# whare_hauora_sensor_r1.net
KiCad netlist of a schematic drawn in EAGLE
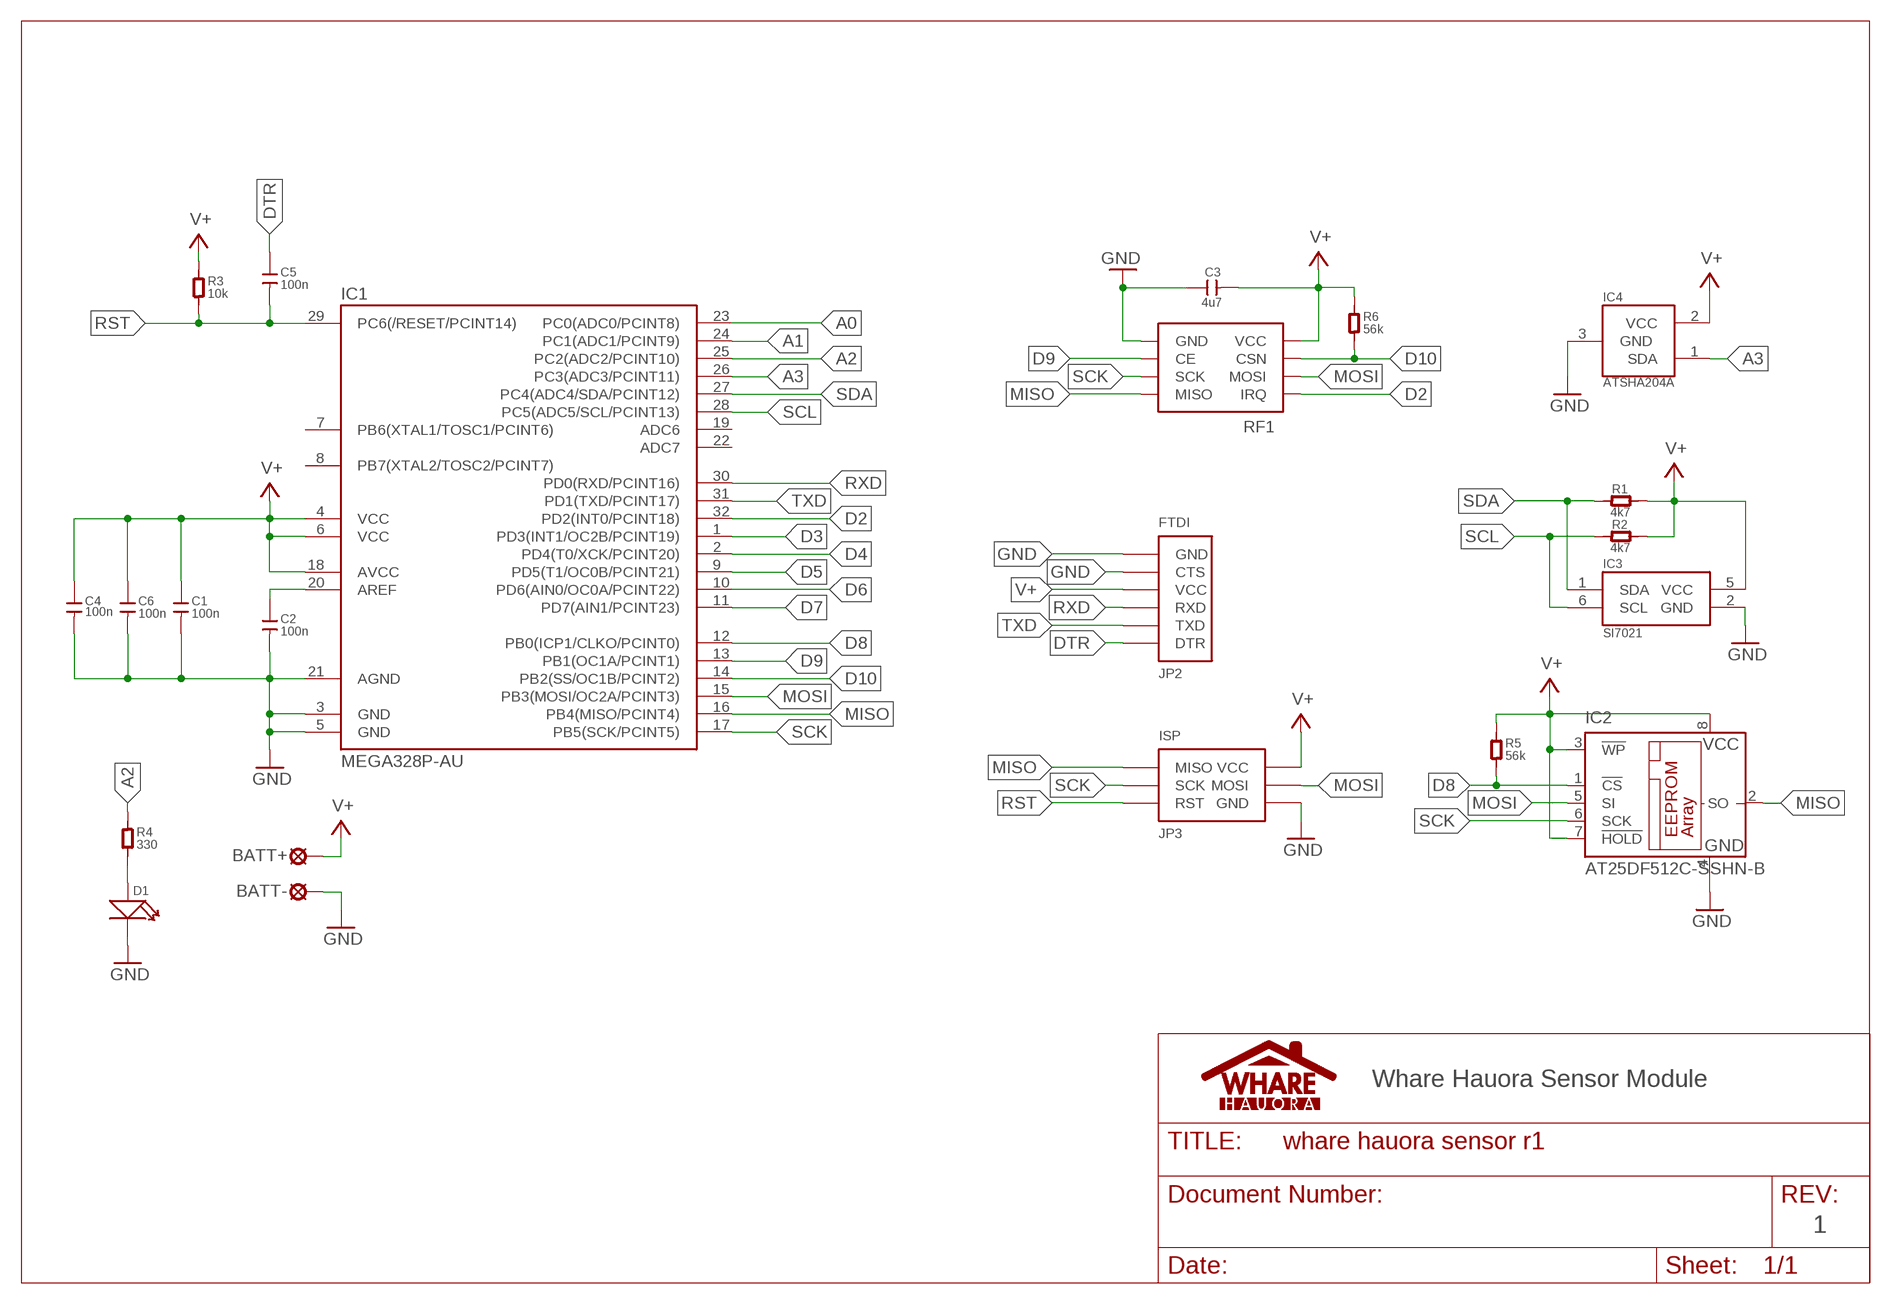
[diagram p0: schematic, sheet 1]

(export (version "E")
  (design (tool "Eeschema 10.0.6"))
  (components
    (comp (ref "BATT+")
      (value "LSP11")
      (footprint "eagle-import:LSP11")
      (libsource (lib "eagle-import") (part "LSP11"))
    )
    (comp (ref "BATT-")
      (value "LSP11")
      (footprint "eagle-import:LSP11")
      (libsource (lib "eagle-import") (part "LSP11"))
    )
    (comp (ref "C1")
      (value "100n")
      (footprint "eagle-import:C0603")
      (libsource (lib "eagle-import") (part "CAP-0603"))
    )
    (comp (ref "C2")
      (value "100n")
      (footprint "eagle-import:C0603")
      (libsource (lib "eagle-import") (part "CAP-0603"))
    )
    (comp (ref "C3")
      (value "4u7")
      (footprint "eagle-import:C0603")
      (libsource (lib "eagle-import") (part "CAP-0603"))
    )
    (comp (ref "C4")
      (value "100n")
      (footprint "eagle-import:C0603")
      (libsource (lib "eagle-import") (part "CAP-0603"))
    )
    (comp (ref "C5")
      (value "100n")
      (footprint "eagle-import:C0603")
      (libsource (lib "eagle-import") (part "CAP-0603"))
    )
    (comp (ref "C6")
      (value "100n")
      (footprint "eagle-import:C0603")
      (libsource (lib "eagle-import") (part "CAP-0603"))
    )
    (comp (ref "D1")
      (value "LED-0603")
      (footprint "eagle-import:LED-0603")
      (libsource (lib "eagle-import") (part "LED-0603"))
    )
    (comp (ref "IC1")
      (value "MEGA328P-AU")
      (footprint "eagle-import:TQFP32-08")
      (libsource (lib "eagle-import") (part "MEGA48/88/168-AU"))
    )
    (comp (ref "IC2")
      (value "AT25DF512C-SSHN-B")
      (footprint "eagle-import:SO-08")
      (fields (field (name "MF") "MICROCHIP") (field (name "MPN") "25AA080/SN"))
      (libsource (lib "eagle-import") (part "25SNAA080"))
    )
    (comp (ref "IC3")
      (value "SI7021")
      (footprint "eagle-import:DFN6")
      (libsource (lib "eagle-import") (part "SI7021"))
    )
    (comp (ref "IC4")
      (value "ATSHA204A")
      (footprint "eagle-import:SOT23")
      (libsource (lib "eagle-import") (part "ATSHA204A"))
    )
    (comp (ref "JP2")
      (value "FTDI")
      (footprint "eagle-import:FTDI")
      (libsource (lib "eagle-import") (part "FTDI"))
    )
    (comp (ref "JP3")
      (value "ISP")
      (footprint "eagle-import:ISP")
      (libsource (lib "eagle-import") (part "ISP"))
    )
    (comp (ref "R1")
      (value "4k7")
      (footprint "eagle-import:R0603")
      (libsource (lib "eagle-import") (part "R-0603"))
    )
    (comp (ref "R2")
      (value "4k7")
      (footprint "eagle-import:R0603")
      (libsource (lib "eagle-import") (part "R-0603"))
    )
    (comp (ref "R3")
      (value "10k")
      (footprint "eagle-import:R0603")
      (libsource (lib "eagle-import") (part "R-0603"))
    )
    (comp (ref "R4")
      (value "330")
      (footprint "eagle-import:R0603")
      (libsource (lib "eagle-import") (part "R-0603"))
    )
    (comp (ref "R5")
      (value "56k")
      (footprint "eagle-import:R0603")
      (libsource (lib "eagle-import") (part "R-0603"))
    )
    (comp (ref "R6")
      (value "56k")
      (footprint "eagle-import:R0603")
      (libsource (lib "eagle-import") (part "R-0603"))
    )
    (comp (ref "RF1")
      (value "NRF24L01+")
      (footprint "eagle-import:NRF24L01+")
      (libsource (lib "eagle-import") (part "NRF24L01+"))
    )
  )
  (nets
    (net (code "1") (name "A0") (class "Default")
      (node (ref "IC1") (pin "23") (pinfunction "PC0(ADC0/PCINT8)_23") (pintype "bidirectional"))
    )
    (net (code "2") (name "A1") (class "Default")
      (node (ref "IC1") (pin "24") (pinfunction "PC1(ADC1/PCINT9)_24") (pintype "bidirectional"))
    )
    (net (code "3") (name "A2") (class "Default")
      (node (ref "IC1") (pin "25") (pinfunction "PC2(ADC2/PCINT10)_25") (pintype "bidirectional"))
      (node (ref "R4") (pin "1") (pinfunction "1_1") (pintype "bidirectional"))
    )
    (net (code "4") (name "A3") (class "Default")
      (node (ref "IC1") (pin "26") (pinfunction "PC3(ADC3/PCINT11)_26") (pintype "bidirectional"))
      (node (ref "IC4") (pin "1") (pinfunction "SDA_1") (pintype "bidirectional"))
    )
    (net (code "5") (name "D2") (class "Default")
      (node (ref "IC1") (pin "32") (pinfunction "PD2(INT0/PCINT18)_32") (pintype "bidirectional"))
      (node (ref "RF1") (pin "P$8") (pinfunction "IRQ_P$8") (pintype "bidirectional"))
    )
    (net (code "6") (name "D3") (class "Default")
      (node (ref "IC1") (pin "1") (pinfunction "PD3(INT1/OC2B/PCINT19)_1") (pintype "bidirectional"))
    )
    (net (code "7") (name "D4") (class "Default")
      (node (ref "IC1") (pin "2") (pinfunction "PD4(T0/XCK/PCINT20)_2") (pintype "bidirectional"))
    )
    (net (code "8") (name "D5") (class "Default")
      (node (ref "IC1") (pin "9") (pinfunction "PD5(T1/OC0B/PCINT21)_9") (pintype "bidirectional"))
    )
    (net (code "9") (name "D6") (class "Default")
      (node (ref "IC1") (pin "10") (pinfunction "PD6(AIN0/OC0A/PCINT22)_10") (pintype "bidirectional"))
    )
    (net (code "10") (name "D7") (class "Default")
      (node (ref "IC1") (pin "11") (pinfunction "PD7(AIN1/PCINT23)_11") (pintype "bidirectional"))
    )
    (net (code "11") (name "D8") (class "Default")
      (node (ref "IC1") (pin "12") (pinfunction "PB0(ICP1/CLKO/PCINT0)_12") (pintype "bidirectional"))
      (node (ref "IC2") (pin "1") (pinfunction "~{CS}_1") (pintype "input"))
      (node (ref "R5") (pin "1") (pinfunction "1_1") (pintype "bidirectional"))
    )
    (net (code "12") (name "D9") (class "Default")
      (node (ref "IC1") (pin "13") (pinfunction "PB1(OC1A/PCINT1)_13") (pintype "bidirectional"))
      (node (ref "RF1") (pin "P$3") (pinfunction "CE_P$3") (pintype "bidirectional"))
    )
    (net (code "13") (name "D10") (class "Default")
      (node (ref "IC1") (pin "14") (pinfunction "PB2(SS/OC1B/PCINT2)_14") (pintype "bidirectional"))
      (node (ref "R6") (pin "1") (pinfunction "1_1") (pintype "bidirectional"))
      (node (ref "RF1") (pin "P$4") (pinfunction "CSN_P$4") (pintype "bidirectional"))
    )
    (net (code "14") (name "DTR") (class "Default")
      (node (ref "C5") (pin "1") (pinfunction "1_1") (pintype "passive"))
      (node (ref "JP2") (pin "DTR") (pinfunction "DTR_DTR") (pintype "bidirectional"))
    )
    (net (code "15") (name "GND") (class "Default")
      (node (ref "BATT-") (pin "MP") (pinfunction "MP_MP") (pintype "passive"))
      (node (ref "C1") (pin "2") (pinfunction "2_2") (pintype "passive"))
      (node (ref "C2") (pin "2") (pinfunction "2_2") (pintype "passive"))
      (node (ref "C3") (pin "1") (pinfunction "1_1") (pintype "passive"))
      (node (ref "C4") (pin "2") (pinfunction "2_2") (pintype "passive"))
      (node (ref "C6") (pin "2") (pinfunction "2_2") (pintype "passive"))
      (node (ref "D1") (pin "-") (pinfunction "-_-") (pintype "passive"))
      (node (ref "IC1") (pin "21") (pinfunction "AGND_21") (pintype "power_in"))
      (node (ref "IC1") (pin "3") (pinfunction "GND_3") (pintype "power_in"))
      (node (ref "IC1") (pin "5") (pinfunction "GND_5") (pintype "power_in"))
      (node (ref "IC2") (pin "4") (pinfunction "GND_4") (pintype "power_in"))
      (node (ref "IC3") (pin "2") (pinfunction "GND_2") (pintype "bidirectional"))
      (node (ref "IC4") (pin "3") (pinfunction "GND_3") (pintype "bidirectional"))
      (node (ref "JP2") (pin "CTS") (pinfunction "CTS_CTS") (pintype "bidirectional"))
      (node (ref "JP2") (pin "GND") (pinfunction "GND_GND") (pintype "bidirectional"))
      (node (ref "JP3") (pin "GND") (pinfunction "GND_GND") (pintype "bidirectional"))
      (node (ref "RF1") (pin "P$1") (pinfunction "GND_P$1") (pintype "bidirectional"))
    )
    (net (code "16") (name "MISO") (class "Default")
      (node (ref "IC1") (pin "16") (pinfunction "PB4(MISO/PCINT4)_16") (pintype "bidirectional"))
      (node (ref "IC2") (pin "2") (pinfunction "SO_2") (pintype "bidirectional"))
      (node (ref "JP3") (pin "MISO") (pinfunction "MISO_MISO") (pintype "bidirectional"))
      (node (ref "RF1") (pin "P$7") (pinfunction "MISO_P$7") (pintype "bidirectional"))
    )
    (net (code "17") (name "MOSI") (class "Default")
      (node (ref "IC1") (pin "15") (pinfunction "PB3(MOSI/OC2A/PCINT3)_15") (pintype "bidirectional"))
      (node (ref "IC2") (pin "5") (pinfunction "SI_5") (pintype "input"))
      (node (ref "JP3") (pin "MOSI") (pinfunction "MOSI_MOSI") (pintype "bidirectional"))
      (node (ref "RF1") (pin "P$6") (pinfunction "MOSI_P$6") (pintype "bidirectional"))
    )
    (net (code "18") (name "Net-(D1-Pad+)") (class "Default")
      (node (ref "D1") (pin "+") (pinfunction "+_+") (pintype "passive"))
      (node (ref "R4") (pin "2") (pinfunction "2_2") (pintype "bidirectional"))
    )
    (net (code "19") (name "Net-(IC1-AREF)") (class "Default")
      (node (ref "C2") (pin "1") (pinfunction "1_1") (pintype "passive"))
      (node (ref "IC1") (pin "20") (pinfunction "AREF_20") (pintype "passive"))
    )
    (net (code "20") (name "RST") (class "Default")
      (node (ref "C5") (pin "2") (pinfunction "2_2") (pintype "passive"))
      (node (ref "IC1") (pin "29") (pinfunction "PC6(/RESET/PCINT14)_29") (pintype "bidirectional"))
      (node (ref "JP3") (pin "RST") (pinfunction "RST_RST") (pintype "bidirectional"))
      (node (ref "R3") (pin "1") (pinfunction "1_1") (pintype "bidirectional"))
    )
    (net (code "21") (name "RXD") (class "Default")
      (node (ref "IC1") (pin "30") (pinfunction "PD0(RXD/PCINT16)_30") (pintype "bidirectional"))
      (node (ref "JP2") (pin "RXD") (pinfunction "RXD_RXD") (pintype "bidirectional"))
    )
    (net (code "22") (name "SCK") (class "Default")
      (node (ref "IC1") (pin "17") (pinfunction "PB5(SCK/PCINT5)_17") (pintype "bidirectional"))
      (node (ref "IC2") (pin "6") (pinfunction "SCK_6") (pintype "input"))
      (node (ref "JP3") (pin "SCK") (pinfunction "SCK_SCK") (pintype "bidirectional"))
      (node (ref "RF1") (pin "P$5") (pinfunction "SCK_P$5") (pintype "bidirectional"))
    )
    (net (code "23") (name "SCL") (class "Default")
      (node (ref "IC1") (pin "28") (pinfunction "PC5(ADC5/SCL/PCINT13)_28") (pintype "bidirectional"))
      (node (ref "IC3") (pin "6") (pinfunction "SCL_6") (pintype "bidirectional"))
      (node (ref "R2") (pin "1") (pinfunction "1_1") (pintype "bidirectional"))
    )
    (net (code "24") (name "SDA") (class "Default")
      (node (ref "IC1") (pin "27") (pinfunction "PC4(ADC4/SDA/PCINT12)_27") (pintype "bidirectional"))
      (node (ref "IC3") (pin "1") (pinfunction "SDA_1") (pintype "bidirectional"))
      (node (ref "R1") (pin "1") (pinfunction "1_1") (pintype "bidirectional"))
    )
    (net (code "25") (name "TXD") (class "Default")
      (node (ref "IC1") (pin "31") (pinfunction "PD1(TXD/PCINT17)_31") (pintype "bidirectional"))
      (node (ref "JP2") (pin "TXD") (pinfunction "TXD_TXD") (pintype "bidirectional"))
    )
    (net (code "26") (name "V+") (class "Default")
      (node (ref "BATT+") (pin "MP") (pinfunction "MP_MP") (pintype "passive"))
      (node (ref "C1") (pin "1") (pinfunction "1_1") (pintype "passive"))
      (node (ref "C3") (pin "2") (pinfunction "2_2") (pintype "passive"))
      (node (ref "C4") (pin "1") (pinfunction "1_1") (pintype "passive"))
      (node (ref "C6") (pin "1") (pinfunction "1_1") (pintype "passive"))
      (node (ref "IC1") (pin "18") (pinfunction "AVCC_18") (pintype "passive"))
      (node (ref "IC1") (pin "4") (pinfunction "VCC_4") (pintype "power_in"))
      (node (ref "IC1") (pin "6") (pinfunction "VCC_6") (pintype "power_in"))
      (node (ref "IC2") (pin "3") (pinfunction "~{WP}_3") (pintype "input"))
      (node (ref "IC2") (pin "7") (pinfunction "~{HOLD}_7") (pintype "input"))
      (node (ref "IC2") (pin "8") (pinfunction "VCC_8") (pintype "power_in"))
      (node (ref "IC3") (pin "5") (pinfunction "VCC_5") (pintype "bidirectional"))
      (node (ref "IC4") (pin "2") (pinfunction "VCC_2") (pintype "bidirectional"))
      (node (ref "JP2") (pin "VCC") (pinfunction "VCC_VCC") (pintype "bidirectional"))
      (node (ref "JP3") (pin "VCC") (pinfunction "VCC_VCC") (pintype "bidirectional"))
      (node (ref "R1") (pin "2") (pinfunction "2_2") (pintype "bidirectional"))
      (node (ref "R2") (pin "2") (pinfunction "2_2") (pintype "bidirectional"))
      (node (ref "R3") (pin "2") (pinfunction "2_2") (pintype "bidirectional"))
      (node (ref "R5") (pin "2") (pinfunction "2_2") (pintype "bidirectional"))
      (node (ref "R6") (pin "2") (pinfunction "2_2") (pintype "bidirectional"))
      (node (ref "RF1") (pin "P$2") (pinfunction "VCC_P$2") (pintype "bidirectional"))
    )
    (net (code "27") (name "unconnected-(IC1-ADC6-Pad19)") (class "Default")
      (node (ref "IC1") (pin "19") (pinfunction "ADC6_19") (pintype "passive"))
    )
    (net (code "28") (name "unconnected-(IC1-ADC7-Pad22)") (class "Default")
      (node (ref "IC1") (pin "22") (pinfunction "ADC7_22") (pintype "passive"))
    )
    (net (code "29") (name "unconnected-(IC1-PB6(XTAL1{slash}TOSC1{slash}PCINT6)-Pad7)") (class "Default")
      (node (ref "IC1") (pin "7") (pinfunction "PB6(XTAL1/TOSC1/PCINT6)_7") (pintype "bidirectional"))
    )
    (net (code "30") (name "unconnected-(IC1-PB7(XTAL2{slash}TOSC2{slash}PCINT7)-Pad8)") (class "Default")
      (node (ref "IC1") (pin "8") (pinfunction "PB7(XTAL2/TOSC2/PCINT7)_8") (pintype "bidirectional"))
    )
  )
)
